# Mood-Badge.net
KiCad netlist of a schematic drawn in EAGLE
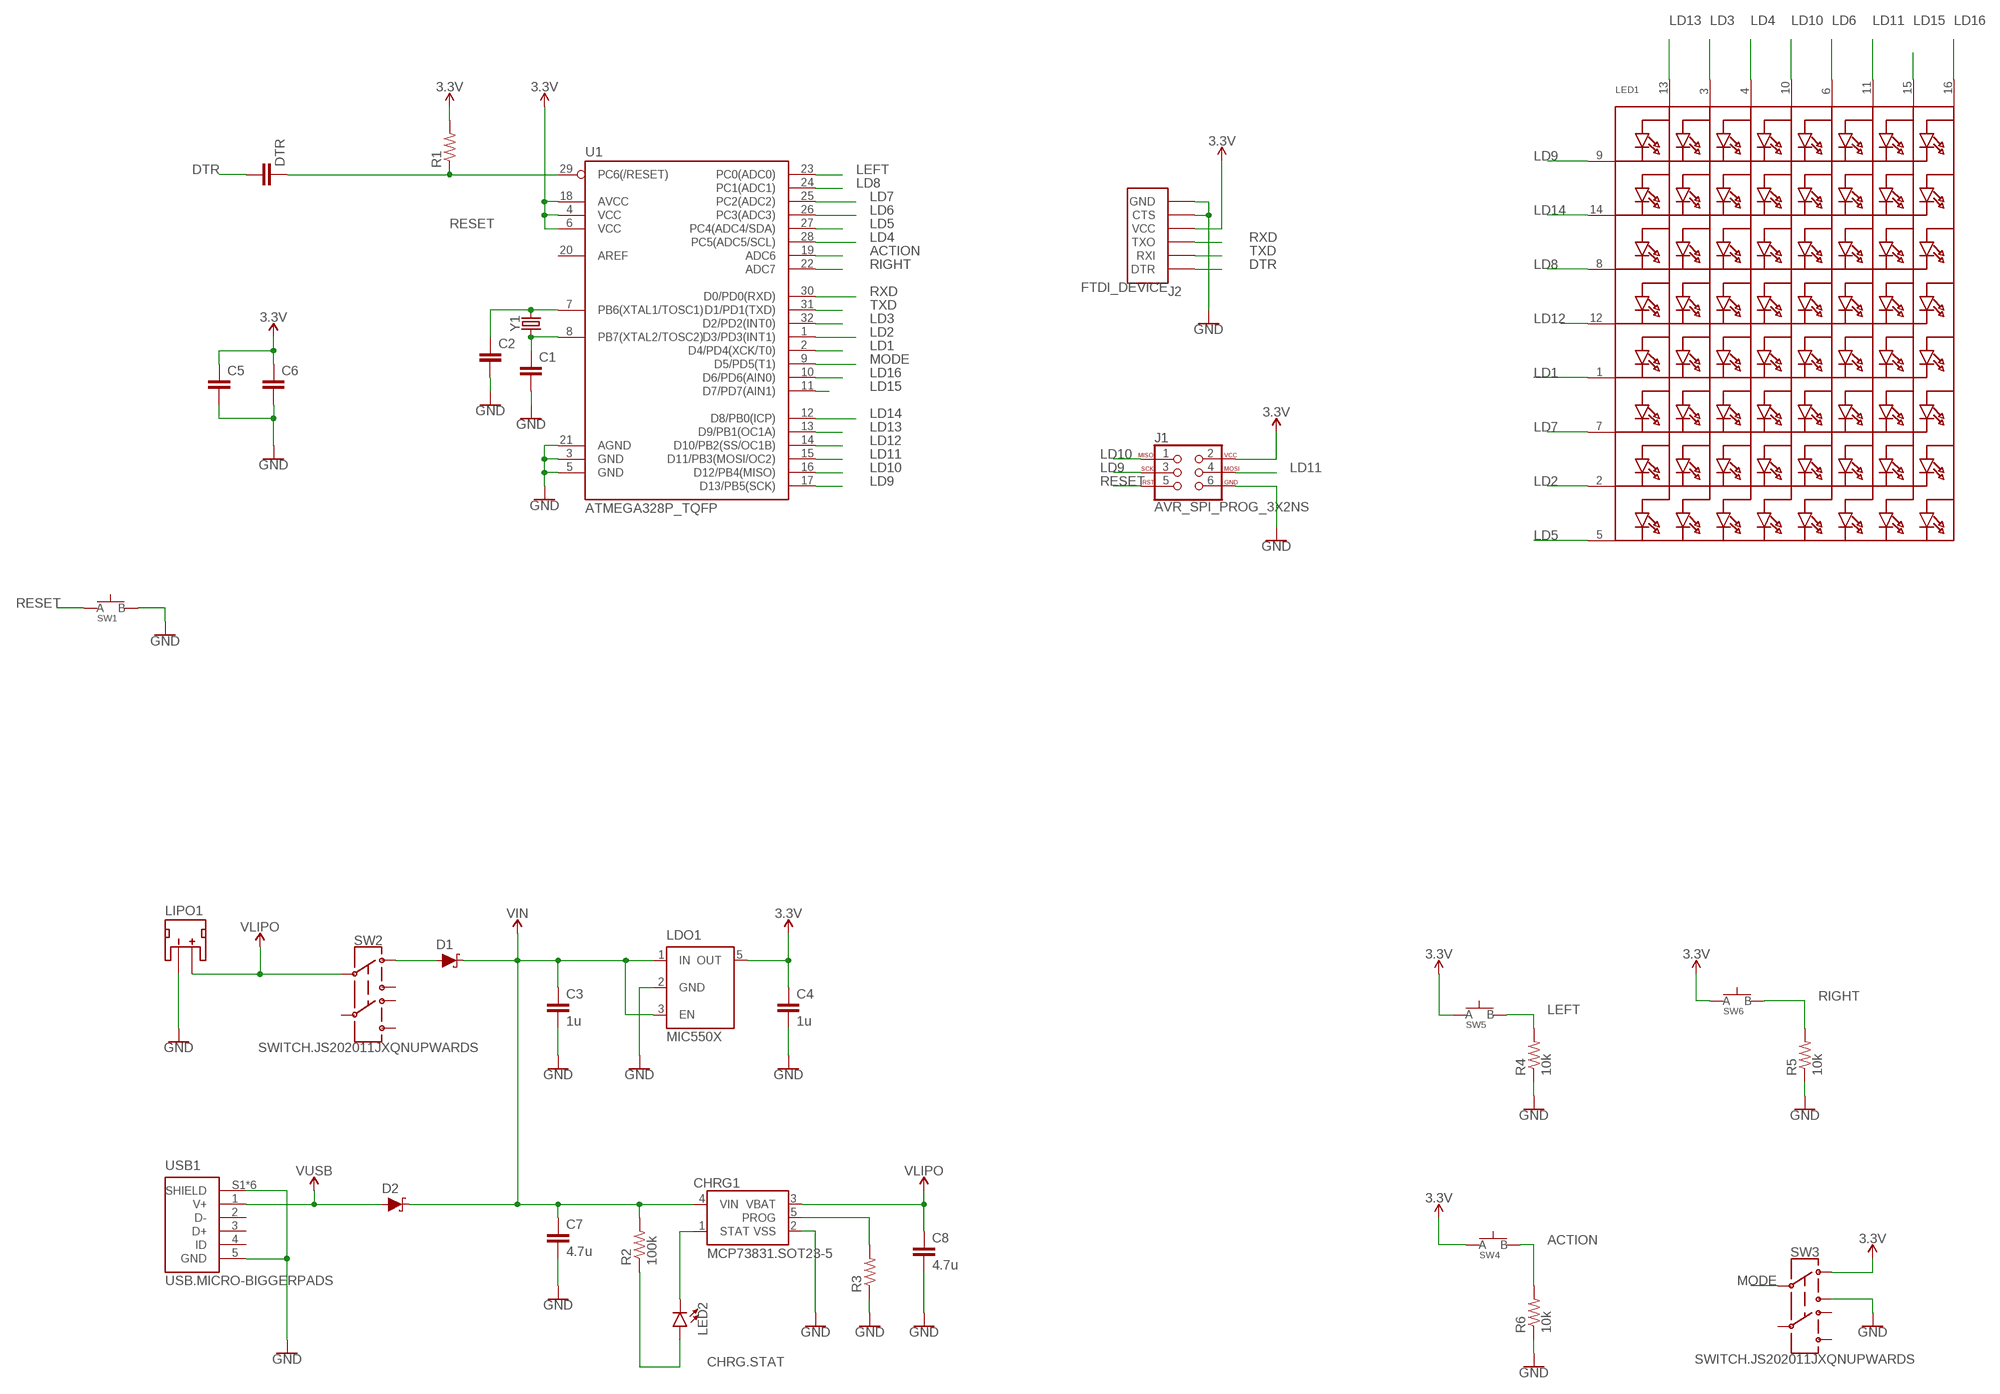
[diagram p0: schematic, sheet 1]

(export (version "E")
  (design (tool "Eeschema 10.0.6"))
  (components
    (comp (ref "C1")
      (value "CAPACITOR0603")
      (footprint "eagle-import:C0603")
      (libsource (lib "eagle-import") (part "CAPACITOR0603"))
    )
    (comp (ref "C2")
      (value "CAPACITOR0603")
      (footprint "eagle-import:C0603")
      (libsource (lib "eagle-import") (part "CAPACITOR0603"))
    )
    (comp (ref "C3")
      (value "1u")
      (footprint "eagle-import:C0603")
      (libsource (lib "eagle-import") (part "CAPACITOR0603"))
    )
    (comp (ref "C4")
      (value "1u")
      (footprint "eagle-import:C0603")
      (libsource (lib "eagle-import") (part "CAPACITOR0603"))
    )
    (comp (ref "C5")
      (value "CAPACITOR0603")
      (footprint "eagle-import:C0603")
      (libsource (lib "eagle-import") (part "CAPACITOR0603"))
    )
    (comp (ref "C6")
      (value "CAPACITOR0603")
      (footprint "eagle-import:C0603")
      (libsource (lib "eagle-import") (part "CAPACITOR0603"))
    )
    (comp (ref "C7")
      (value "4.7u")
      (footprint "eagle-import:C0603")
      (libsource (lib "eagle-import") (part "CAPACITOR0603"))
    )
    (comp (ref "C8")
      (value "4.7u")
      (footprint "eagle-import:C0603")
      (libsource (lib "eagle-import") (part "CAPACITOR0603"))
    )
    (comp (ref "CHRG1")
      (value "MCP73831.SOT23-5")
      (footprint "eagle-import:SOT23-5")
      (libsource (lib "eagle-import") (part "MCP73831.SOT23-5"))
    )
    (comp (ref "D1")
      (value "SCHOTTKY-USC")
      (footprint "eagle-import:USC")
      (libsource (lib "eagle-import") (part "SCHOTTKY-USC"))
    )
    (comp (ref "D2")
      (value "SCHOTTKY-USC")
      (footprint "eagle-import:USC")
      (libsource (lib "eagle-import") (part "SCHOTTKY-USC"))
    )
    (comp (ref "DTR")
      (value "CAPACITOR0603")
      (footprint "eagle-import:C0603")
      (libsource (lib "eagle-import") (part "CAPACITOR0603"))
    )
    (comp (ref "J1")
      (value "AVR_SPI_PROG_3X2NS")
      (footprint "eagle-import:2X3-NS")
      (libsource (lib "eagle-import") (part "AVR_SPI_PROG_3X2NS"))
    )
    (comp (ref "J2")
      (value "FTDI_DEVICE")
      (footprint "eagle-import:FTDI_DEVICE")
      (libsource (lib "eagle-import") (part "FTDI_DEVICE"))
    )
    (comp (ref "LDO1")
      (value "MIC550X")
      (footprint "eagle-import:SOT23-5")
      (libsource (lib "eagle-import") (part "MIC550X"))
    )
    (comp (ref "LED1")
      (value "DOTMATRIX_8X8_ROWCATHODEM12A881UR")
      (footprint "eagle-import:DOTMATRIX_BL-M12A881UR")
      (libsource (lib "eagle-import") (part "DOTMATRIX_8X8_ROWCATHODEM12A881UR"))
    )
    (comp (ref "LED2")
      (value "LED0805")
      (footprint "eagle-import:LED-0805")
      (libsource (lib "eagle-import") (part "LED0805"))
    )
    (comp (ref "LIPO1")
      (value "JST_2MM_MALE")
      (footprint "eagle-import:JST-2-SMD")
      (libsource (lib "eagle-import") (part "JST_2MM_MALE"))
    )
    (comp (ref "R1")
      (value "RESISTOR0603")
      (footprint "eagle-import:R0603")
      (libsource (lib "eagle-import") (part "RESISTOR0603"))
    )
    (comp (ref "R2")
      (value "100k")
      (footprint "eagle-import:R0603")
      (libsource (lib "eagle-import") (part "RESISTOR0603"))
    )
    (comp (ref "R3")
      (value "RESISTOR0603")
      (footprint "eagle-import:R0603")
      (libsource (lib "eagle-import") (part "RESISTOR0603"))
    )
    (comp (ref "R4")
      (value "10k")
      (footprint "eagle-import:R0603")
      (libsource (lib "eagle-import") (part "RESISTOR0603"))
    )
    (comp (ref "R5")
      (value "10k")
      (footprint "eagle-import:R0603")
      (libsource (lib "eagle-import") (part "RESISTOR0603"))
    )
    (comp (ref "R6")
      (value "10k")
      (footprint "eagle-import:R0603")
      (libsource (lib "eagle-import") (part "RESISTOR0603"))
    )
    (comp (ref "SW1")
      (value "SPST.KT11P4SM34LFS")
      (footprint "eagle-import:SPST.KT11P4SM34LFS")
      (libsource (lib "eagle-import") (part "SPST.KT11P4SM34LFS"))
    )
    (comp (ref "SW2")
      (value "SWITCH.JS202011JXQNUPWARDS")
      (footprint "eagle-import:SWITCH.00")
      (libsource (lib "eagle-import") (part "SWITCH.JS202011JXQNUPWARDS"))
    )
    (comp (ref "SW3")
      (value "SWITCH.JS202011JXQNUPWARDS")
      (footprint "eagle-import:SWITCH.00")
      (libsource (lib "eagle-import") (part "SWITCH.JS202011JXQNUPWARDS"))
    )
    (comp (ref "SW4")
      (value "SPST.KT11P4SM34LFS")
      (footprint "eagle-import:SPST.KT11P4SM34LFS")
      (libsource (lib "eagle-import") (part "SPST.KT11P4SM34LFS"))
    )
    (comp (ref "SW5")
      (value "SPST.KT11P4SM34LFS")
      (footprint "eagle-import:SPST.KT11P4SM34LFS")
      (libsource (lib "eagle-import") (part "SPST.KT11P4SM34LFS"))
    )
    (comp (ref "SW6")
      (value "SPST.KT11P4SM34LFS")
      (footprint "eagle-import:SPST.KT11P4SM34LFS")
      (libsource (lib "eagle-import") (part "SPST.KT11P4SM34LFS"))
    )
    (comp (ref "U1")
      (value "ATMEGA328P_TQFP")
      (footprint "eagle-import:TQFP32-08")
      (libsource (lib "eagle-import") (part "ATMEGA328P_TQFP"))
    )
    (comp (ref "USB1")
      (value "USB.MICRO-BIGGERPADS")
      (footprint "eagle-import:USB-MICRO-01.BIGGERPADS")
      (libsource (lib "eagle-import") (part "USB.MICRO-BIGGERPADS"))
    )
    (comp (ref "Y1")
      (value "CRYSTAL-CA-310")
      (footprint "eagle-import:CA-301")
      (libsource (lib "eagle-import") (part "CRYSTAL-CA-310"))
    )
  )
  (nets
    (net (code "1") (name "/ACTION") (class "Default")
      (node (ref "R6") (pin "2") (pinfunction "2_2") (pintype "passive"))
      (node (ref "SW4") (pin "3") (pinfunction "B_3") (pintype "bidirectional"))
      (node (ref "SW4") (pin "4") (pinfunction "B_4") (pintype "bidirectional"))
      (node (ref "U1") (pin "19") (pinfunction "ADC6_19") (pintype "bidirectional"))
    )
    (net (code "2") (name "/CHRG.STAT") (class "Default")
      (node (ref "LED2") (pin "A") (pinfunction "A_A") (pintype "passive"))
      (node (ref "R2") (pin "1") (pinfunction "1_1") (pintype "passive"))
    )
    (net (code "3") (name "/DTR") (class "Default")
      (node (ref "DTR") (pin "1") (pinfunction "1_1") (pintype "passive"))
      (node (ref "J2") (pin "DTR") (pinfunction "DTR_DTR") (pintype "bidirectional"))
    )
    (net (code "4") (name "/LD1") (class "Default")
      (node (ref "LED1") (pin "1") (pinfunction "K5_1") (pintype "bidirectional"))
      (node (ref "U1") (pin "2") (pinfunction "D4/PD4(XCK/T0)_2") (pintype "bidirectional"))
    )
    (net (code "5") (name "/LD2") (class "Default")
      (node (ref "LED1") (pin "2") (pinfunction "K7_2") (pintype "bidirectional"))
      (node (ref "U1") (pin "1") (pinfunction "D3/PD3(INT1)_1") (pintype "bidirectional"))
    )
    (net (code "6") (name "/LD3") (class "Default")
      (node (ref "LED1") (pin "3") (pinfunction "A2_3") (pintype "bidirectional"))
      (node (ref "U1") (pin "32") (pinfunction "D2/PD2(INT0)_32") (pintype "bidirectional"))
    )
    (net (code "7") (name "/LD4") (class "Default")
      (node (ref "LED1") (pin "4") (pinfunction "A3_4") (pintype "bidirectional"))
      (node (ref "U1") (pin "28") (pinfunction "PC5(ADC5/SCL)_28") (pintype "bidirectional"))
    )
    (net (code "8") (name "/LD5") (class "Default")
      (node (ref "LED1") (pin "5") (pinfunction "K8_5") (pintype "bidirectional"))
      (node (ref "U1") (pin "27") (pinfunction "PC4(ADC4/SDA)_27") (pintype "bidirectional"))
    )
    (net (code "9") (name "/LD6") (class "Default")
      (node (ref "LED1") (pin "6") (pinfunction "A5_6") (pintype "bidirectional"))
      (node (ref "U1") (pin "26") (pinfunction "PC3(ADC3)_26") (pintype "bidirectional"))
    )
    (net (code "10") (name "/LD7") (class "Default")
      (node (ref "LED1") (pin "7") (pinfunction "K6_7") (pintype "bidirectional"))
      (node (ref "U1") (pin "25") (pinfunction "PC2(ADC2)_25") (pintype "bidirectional"))
    )
    (net (code "11") (name "/LD8") (class "Default")
      (node (ref "LED1") (pin "8") (pinfunction "K3_8") (pintype "bidirectional"))
      (node (ref "U1") (pin "24") (pinfunction "PC1(ADC1)_24") (pintype "bidirectional"))
    )
    (net (code "12") (name "/LD9") (class "Default")
      (node (ref "J1") (pin "3") (pinfunction "3_3") (pintype "passive"))
      (node (ref "LED1") (pin "9") (pinfunction "K1_9") (pintype "bidirectional"))
      (node (ref "U1") (pin "17") (pinfunction "D13/PB5(SCK)_17") (pintype "bidirectional"))
    )
    (net (code "13") (name "/LD10") (class "Default")
      (node (ref "J1") (pin "1") (pinfunction "1_1") (pintype "passive"))
      (node (ref "LED1") (pin "10") (pinfunction "A4_10") (pintype "bidirectional"))
      (node (ref "U1") (pin "16") (pinfunction "D12/PB4(MISO)_16") (pintype "bidirectional"))
    )
    (net (code "14") (name "/LD11") (class "Default")
      (node (ref "J1") (pin "4") (pinfunction "4_4") (pintype "passive"))
      (node (ref "LED1") (pin "11") (pinfunction "A6_11") (pintype "bidirectional"))
      (node (ref "U1") (pin "15") (pinfunction "D11/PB3(MOSI/OC2)_15") (pintype "bidirectional"))
    )
    (net (code "15") (name "/LD12") (class "Default")
      (node (ref "LED1") (pin "12") (pinfunction "K4_12") (pintype "bidirectional"))
      (node (ref "U1") (pin "14") (pinfunction "D10/PB2(SS/OC1B)_14") (pintype "bidirectional"))
    )
    (net (code "16") (name "/LD13") (class "Default")
      (node (ref "LED1") (pin "13") (pinfunction "A1_13") (pintype "bidirectional"))
      (node (ref "U1") (pin "13") (pinfunction "D9/PB1(OC1A)_13") (pintype "bidirectional"))
    )
    (net (code "17") (name "/LD14") (class "Default")
      (node (ref "LED1") (pin "14") (pinfunction "K2_14") (pintype "bidirectional"))
      (node (ref "U1") (pin "12") (pinfunction "D8/PB0(ICP)_12") (pintype "bidirectional"))
    )
    (net (code "18") (name "/LD15") (class "Default")
      (node (ref "LED1") (pin "15") (pinfunction "A7_15") (pintype "bidirectional"))
      (node (ref "U1") (pin "11") (pinfunction "D7/PD7(AIN1)_11") (pintype "bidirectional"))
    )
    (net (code "19") (name "/LD16") (class "Default")
      (node (ref "LED1") (pin "16") (pinfunction "A8_16") (pintype "bidirectional"))
      (node (ref "U1") (pin "10") (pinfunction "D6/PD6(AIN0)_10") (pintype "bidirectional"))
    )
    (net (code "20") (name "/LEFT") (class "Default")
      (node (ref "R4") (pin "2") (pinfunction "2_2") (pintype "passive"))
      (node (ref "SW5") (pin "3") (pinfunction "B_3") (pintype "bidirectional"))
      (node (ref "SW5") (pin "4") (pinfunction "B_4") (pintype "bidirectional"))
      (node (ref "U1") (pin "23") (pinfunction "PC0(ADC0)_23") (pintype "bidirectional"))
    )
    (net (code "21") (name "/MODE") (class "Default")
      (node (ref "SW3") (pin "2") (pinfunction "2_2") (pintype "bidirectional"))
      (node (ref "U1") (pin "9") (pinfunction "D5/PD5(T1)_9") (pintype "bidirectional"))
    )
    (net (code "22") (name "/RESET") (class "Default")
      (node (ref "DTR") (pin "2") (pinfunction "2_2") (pintype "passive"))
      (node (ref "J1") (pin "5") (pinfunction "5_5") (pintype "passive"))
      (node (ref "R1") (pin "1") (pinfunction "1_1") (pintype "passive"))
      (node (ref "SW1") (pin "1") (pinfunction "A_1") (pintype "bidirectional"))
      (node (ref "SW1") (pin "2") (pinfunction "A_2") (pintype "bidirectional"))
      (node (ref "U1") (pin "29") (pinfunction "PC6(/RESET)_29") (pintype "bidirectional"))
    )
    (net (code "23") (name "/RIGHT") (class "Default")
      (node (ref "R5") (pin "2") (pinfunction "2_2") (pintype "passive"))
      (node (ref "SW6") (pin "3") (pinfunction "B_3") (pintype "bidirectional"))
      (node (ref "SW6") (pin "4") (pinfunction "B_4") (pintype "bidirectional"))
      (node (ref "U1") (pin "22") (pinfunction "ADC7_22") (pintype "bidirectional"))
    )
    (net (code "24") (name "/RXD") (class "Default")
      (node (ref "J2") (pin "RXI") (pinfunction "TXO_RXI") (pintype "bidirectional"))
      (node (ref "U1") (pin "30") (pinfunction "D0/PD0(RXD)_30") (pintype "bidirectional"))
    )
    (net (code "25") (name "/TXD") (class "Default")
      (node (ref "J2") (pin "TXO") (pinfunction "RXI_TXO") (pintype "bidirectional"))
      (node (ref "U1") (pin "31") (pinfunction "D1/PD1(TXD)_31") (pintype "bidirectional"))
    )
    (net (code "26") (name "3.3V") (class "Default")
      (node (ref "C4") (pin "1") (pinfunction "1_1") (pintype "passive"))
      (node (ref "C5") (pin "1") (pinfunction "1_1") (pintype "passive"))
      (node (ref "C6") (pin "1") (pinfunction "1_1") (pintype "passive"))
      (node (ref "J1") (pin "2") (pinfunction "2_2") (pintype "passive"))
      (node (ref "J2") (pin "VCC") (pinfunction "VCC_VCC") (pintype "bidirectional"))
      (node (ref "LDO1") (pin "5") (pinfunction "OUT_5") (pintype "bidirectional"))
      (node (ref "R1") (pin "2") (pinfunction "2_2") (pintype "passive"))
      (node (ref "SW3") (pin "1") (pinfunction "1_1") (pintype "bidirectional"))
      (node (ref "SW4") (pin "1") (pinfunction "A_1") (pintype "bidirectional"))
      (node (ref "SW4") (pin "2") (pinfunction "A_2") (pintype "bidirectional"))
      (node (ref "SW5") (pin "1") (pinfunction "A_1") (pintype "bidirectional"))
      (node (ref "SW5") (pin "2") (pinfunction "A_2") (pintype "bidirectional"))
      (node (ref "SW6") (pin "1") (pinfunction "A_1") (pintype "bidirectional"))
      (node (ref "SW6") (pin "2") (pinfunction "A_2") (pintype "bidirectional"))
      (node (ref "U1") (pin "18") (pinfunction "AVCC_18") (pintype "bidirectional"))
      (node (ref "U1") (pin "4") (pinfunction "VCC_4") (pintype "bidirectional"))
      (node (ref "U1") (pin "6") (pinfunction "VCC_6") (pintype "bidirectional"))
    )
    (net (code "27") (name "GND") (class "Default")
      (node (ref "C1") (pin "2") (pinfunction "2_2") (pintype "passive"))
      (node (ref "C2") (pin "2") (pinfunction "2_2") (pintype "passive"))
      (node (ref "C3") (pin "2") (pinfunction "2_2") (pintype "passive"))
      (node (ref "C4") (pin "2") (pinfunction "2_2") (pintype "passive"))
      (node (ref "C5") (pin "2") (pinfunction "2_2") (pintype "passive"))
      (node (ref "C6") (pin "2") (pinfunction "2_2") (pintype "passive"))
      (node (ref "C7") (pin "2") (pinfunction "2_2") (pintype "passive"))
      (node (ref "C8") (pin "2") (pinfunction "2_2") (pintype "passive"))
      (node (ref "CHRG1") (pin "2") (pinfunction "VSS_2") (pintype "power_in"))
      (node (ref "J1") (pin "6") (pinfunction "6_6") (pintype "passive"))
      (node (ref "J2") (pin "CTS") (pinfunction "CTS_CTS") (pintype "bidirectional"))
      (node (ref "J2") (pin "GND") (pinfunction "GND_GND") (pintype "bidirectional"))
      (node (ref "LDO1") (pin "2") (pinfunction "GND_2") (pintype "bidirectional"))
      (node (ref "LIPO1") (pin "1") (pinfunction "-_1") (pintype "bidirectional"))
      (node (ref "R3") (pin "1") (pinfunction "1_1") (pintype "passive"))
      (node (ref "R4") (pin "1") (pinfunction "1_1") (pintype "passive"))
      (node (ref "R5") (pin "1") (pinfunction "1_1") (pintype "passive"))
      (node (ref "R6") (pin "1") (pinfunction "1_1") (pintype "passive"))
      (node (ref "SW1") (pin "3") (pinfunction "B_3") (pintype "bidirectional"))
      (node (ref "SW1") (pin "4") (pinfunction "B_4") (pintype "bidirectional"))
      (node (ref "SW3") (pin "3") (pinfunction "3_3") (pintype "bidirectional"))
      (node (ref "U1") (pin "21") (pinfunction "AGND_21") (pintype "bidirectional"))
      (node (ref "U1") (pin "3") (pinfunction "GND_3") (pintype "bidirectional"))
      (node (ref "U1") (pin "5") (pinfunction "GND_5") (pintype "bidirectional"))
      (node (ref "USB1") (pin "5") (pinfunction "GND_5") (pintype "bidirectional"))
      (node (ref "USB1") (pin "S1") (pinfunction "SHIELD_S1") (pintype "bidirectional"))
      (node (ref "USB1") (pin "S2") (pinfunction "SHIELD_S2") (pintype "bidirectional"))
      (node (ref "USB1") (pin "S3") (pinfunction "SHIELD_S3") (pintype "bidirectional"))
      (node (ref "USB1") (pin "S4") (pinfunction "SHIELD_S4") (pintype "bidirectional"))
      (node (ref "USB1") (pin "S5") (pinfunction "SHIELD_S5") (pintype "bidirectional"))
      (node (ref "USB1") (pin "S6") (pinfunction "SHIELD_S6") (pintype "bidirectional"))
    )
    (net (code "28") (name "Net-(CHRG1-PROG)") (class "Default")
      (node (ref "CHRG1") (pin "5") (pinfunction "PROG_5") (pintype "input"))
      (node (ref "R3") (pin "2") (pinfunction "2_2") (pintype "passive"))
    )
    (net (code "29") (name "Net-(CHRG1-STAT)") (class "Default")
      (node (ref "CHRG1") (pin "1") (pinfunction "STAT_1") (pintype "output"))
      (node (ref "LED2") (pin "C") (pinfunction "C_C") (pintype "passive"))
    )
    (net (code "30") (name "Net-(D1-A)") (class "Default")
      (node (ref "D1") (pin "+") (pinfunction "A_+") (pintype "passive"))
      (node (ref "SW2") (pin "1") (pinfunction "1_1") (pintype "bidirectional"))
    )
    (net (code "31") (name "Net-(U1-PB6(XTAL1{slash}TOSC1))") (class "Default")
      (node (ref "C2") (pin "1") (pinfunction "1_1") (pintype "passive"))
      (node (ref "U1") (pin "7") (pinfunction "PB6(XTAL1/TOSC1)_7") (pintype "bidirectional"))
      (node (ref "Y1") (pin "2") (pinfunction "2_2") (pintype "passive"))
    )
    (net (code "32") (name "Net-(U1-PB7(XTAL2{slash}TOSC2))") (class "Default")
      (node (ref "C1") (pin "1") (pinfunction "1_1") (pintype "passive"))
      (node (ref "U1") (pin "8") (pinfunction "PB7(XTAL2/TOSC2)_8") (pintype "bidirectional"))
      (node (ref "Y1") (pin "1") (pinfunction "1_1") (pintype "passive"))
    )
    (net (code "33") (name "VIN") (class "Default")
      (node (ref "C3") (pin "1") (pinfunction "1_1") (pintype "passive"))
      (node (ref "C7") (pin "1") (pinfunction "1_1") (pintype "passive"))
      (node (ref "CHRG1") (pin "4") (pinfunction "VIN_4") (pintype "power_in"))
      (node (ref "D1") (pin "-") (pinfunction "C_-") (pintype "passive"))
      (node (ref "D2") (pin "-") (pinfunction "C_-") (pintype "passive"))
      (node (ref "LDO1") (pin "1") (pinfunction "IN_1") (pintype "bidirectional"))
      (node (ref "LDO1") (pin "3") (pinfunction "EN_3") (pintype "bidirectional"))
      (node (ref "R2") (pin "2") (pinfunction "2_2") (pintype "passive"))
    )
    (net (code "34") (name "VLIPO") (class "Default")
      (node (ref "C8") (pin "1") (pinfunction "1_1") (pintype "passive"))
      (node (ref "CHRG1") (pin "3") (pinfunction "VBAT_3") (pintype "power_in"))
      (node (ref "LIPO1") (pin "2") (pinfunction "+_2") (pintype "bidirectional"))
      (node (ref "SW2") (pin "2") (pinfunction "2_2") (pintype "bidirectional"))
    )
    (net (code "35") (name "VUSB") (class "Default")
      (node (ref "D2") (pin "+") (pinfunction "A_+") (pintype "passive"))
      (node (ref "USB1") (pin "1") (pinfunction "V+_1") (pintype "bidirectional"))
    )
    (net (code "36") (name "unconnected-(LIPO1-PAD1-PadNC1)") (class "Default")
      (node (ref "LIPO1") (pin "NC1") (pinfunction "PAD1_NC1") (pintype "bidirectional"))
    )
    (net (code "37") (name "unconnected-(LIPO1-PAD2-PadNC2)") (class "Default")
      (node (ref "LIPO1") (pin "NC2") (pinfunction "PAD2_NC2") (pintype "bidirectional"))
    )
    (net (code "38") (name "unconnected-(SW2-4-Pad5)") (class "Default")
      (node (ref "SW2") (pin "5") (pinfunction "4_5") (pintype "bidirectional"))
    )
    (net (code "39") (name "unconnected-(SW2-5-Pad6)") (class "Default")
      (node (ref "SW2") (pin "6") (pinfunction "5_6") (pintype "bidirectional"))
    )
    (net (code "40") (name "unconnected-(SW2-6-Pad7)") (class "Default")
      (node (ref "SW2") (pin "7") (pinfunction "6_7") (pintype "bidirectional"))
    )
    (net (code "41") (name "unconnected-(SW2-Pad3)") (class "Default")
      (node (ref "SW2") (pin "3") (pinfunction "3_3") (pintype "bidirectional"))
    )
    (net (code "42") (name "unconnected-(SW3-4-Pad5)") (class "Default")
      (node (ref "SW3") (pin "5") (pinfunction "4_5") (pintype "bidirectional"))
    )
    (net (code "43") (name "unconnected-(SW3-5-Pad6)") (class "Default")
      (node (ref "SW3") (pin "6") (pinfunction "5_6") (pintype "bidirectional"))
    )
    (net (code "44") (name "unconnected-(SW3-6-Pad7)") (class "Default")
      (node (ref "SW3") (pin "7") (pinfunction "6_7") (pintype "bidirectional"))
    )
    (net (code "45") (name "unconnected-(U1-AREF-Pad20)") (class "Default")
      (node (ref "U1") (pin "20") (pinfunction "AREF_20") (pintype "bidirectional"))
    )
    (net (code "46") (name "unconnected-(USB1-D+-Pad3)") (class "Default")
      (node (ref "USB1") (pin "3") (pinfunction "D+_3") (pintype "bidirectional"))
    )
    (net (code "47") (name "unconnected-(USB1-D--Pad2)") (class "Default")
      (node (ref "USB1") (pin "2") (pinfunction "D-_2") (pintype "bidirectional"))
    )
    (net (code "48") (name "unconnected-(USB1-ID-Pad4)") (class "Default")
      (node (ref "USB1") (pin "4") (pinfunction "ID_4") (pintype "bidirectional"))
    )
  )
)
